# Logic_probe.net
KiCad netlist of a schematic drawn in EAGLE
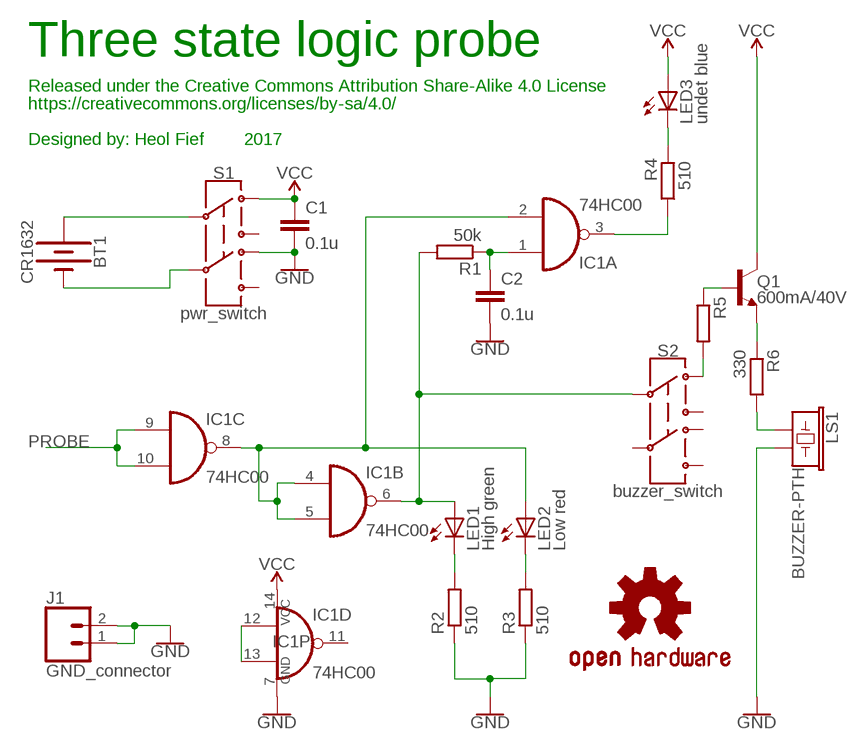
[diagram p0: schematic, sheet 1]

(export (version "E")
  (design (tool "Eeschema 10.0.6"))
  (components
    (comp (ref "BT1")
      (value "CR1632")
      (footprint "eagle-import:BATTCON_12MM_PTH")
      (libsource (lib "eagle-import") (part "BATTERY-12MM_PTH"))
    )
    (comp (ref "C1")
      (value "0.1u")
      (footprint "eagle-import:C0805")
      (libsource (lib "eagle-import") (part "C-EUC0805"))
    )
    (comp (ref "C2")
      (value "0.1u")
      (footprint "eagle-import:C0805")
      (libsource (lib "eagle-import") (part "C-EUC0805"))
    )
    (comp (ref "IC1")
      (value "74HC00")
      (footprint "eagle-import:SO14")
      (libsource (lib "eagle-import") (part "7400DHC"))
    )
    (comp (ref "J1")
      (value "GND_connector")
      (footprint "eagle-import:MOLEX-1X2")
      (libsource (lib "eagle-import") (part "CONN_02POLAR"))
    )
    (comp (ref "LED1")
      (value "High green")
      (footprint "eagle-import:1206")
      (libsource (lib "eagle-import") (part "LEDSMT1206"))
    )
    (comp (ref "LED2")
      (value "Low red")
      (footprint "eagle-import:1206")
      (libsource (lib "eagle-import") (part "LEDSMT1206"))
    )
    (comp (ref "LED3")
      (value "undet blue")
      (footprint "eagle-import:1206")
      (libsource (lib "eagle-import") (part "LEDSMT1206"))
    )
    (comp (ref "LOGO1")
      (value "OSHW-LOGOL")
      (footprint "eagle-import:OSHW-LOGO-L")
      (libsource (lib "eagle-import") (part "OSHW-LOGOL"))
    )
    (comp (ref "LS1")
      (value "BUZZER-PTH")
      (footprint "eagle-import:BUZZER-12MM")
      (libsource (lib "eagle-import") (part "BUZZER-PTH"))
    )
    (comp (ref "Q1")
      (value "600mA/40V")
      (footprint "eagle-import:SOT23-3")
      (libsource (lib "eagle-import") (part "TRANS_NPN-MMBT2222AL"))
    )
    (comp (ref "R1")
      (value "50k")
      (footprint "eagle-import:R1206")
      (libsource (lib "eagle-import") (part "R-EU_R1206"))
    )
    (comp (ref "R2")
      (value "510")
      (footprint "eagle-import:R0805")
      (libsource (lib "eagle-import") (part "R-EU_R0805"))
    )
    (comp (ref "R3")
      (value "510")
      (footprint "eagle-import:R0805")
      (libsource (lib "eagle-import") (part "R-EU_R0805"))
    )
    (comp (ref "R4")
      (value "510")
      (footprint "eagle-import:R0805")
      (libsource (lib "eagle-import") (part "R-EU_R0805"))
    )
    (comp (ref "R5")
      (value "R-EU_R1206")
      (footprint "eagle-import:R1206")
      (libsource (lib "eagle-import") (part "R-EU_R1206"))
    )
    (comp (ref "R6")
      (value "330")
      (footprint "eagle-import:R1206")
      (libsource (lib "eagle-import") (part "R-EU_R1206"))
    )
    (comp (ref "S1")
      (value "pwr_switch")
      (footprint "eagle-import:SWITCH_DPDT_SMD_AYZ0202")
      (libsource (lib "eagle-import") (part "SWITCH-DPDT-SMD-AYZ0202"))
    )
    (comp (ref "S2")
      (value "buzzer_switch")
      (footprint "eagle-import:SWITCH_DPDT_SMD_AYZ0202")
      (libsource (lib "eagle-import") (part "SWITCH-DPDT-SMD-AYZ0202"))
    )
  )
  (nets
    (net (code "1") (name "/PROBE") (class "Default")
      (node (ref "IC1") (pin "10") (pinfunction "I1_10") (pintype "input"))
      (node (ref "IC1") (pin "9") (pinfunction "I0_9") (pintype "input"))
    )
    (net (code "2") (name "GND") (class "Default")
      (node (ref "C1") (pin "2") (pinfunction "2_2") (pintype "passive"))
      (node (ref "C2") (pin "2") (pinfunction "2_2") (pintype "passive"))
      (node (ref "IC1") (pin "7") (pinfunction "GND_7") (pintype "power_in"))
      (node (ref "J1") (pin "1") (pinfunction "1_1") (pintype "passive"))
      (node (ref "J1") (pin "2") (pinfunction "2_2") (pintype "passive"))
      (node (ref "LS1") (pin "-") (pinfunction "2_-") (pintype "passive"))
      (node (ref "R2") (pin "1") (pinfunction "1_1") (pintype "passive"))
      (node (ref "R3") (pin "1") (pinfunction "1_1") (pintype "passive"))
      (node (ref "S1") (pin "4") (pinfunction "4_4") (pintype "bidirectional"))
    )
    (net (code "3") (name "Net-(BT1-+)") (class "Default")
      (node (ref "BT1") (pin "VCC@1") (pinfunction "+_VCC@1") (pintype "power_in"))
      (node (ref "S1") (pin "2") (pinfunction "2_2") (pintype "bidirectional"))
    )
    (net (code "4") (name "Net-(BT1--)") (class "Default")
      (node (ref "BT1") (pin "GND") (pinfunction "-_GND") (pintype "power_in"))
      (node (ref "S1") (pin "5") (pinfunction "5_5") (pintype "bidirectional"))
    )
    (net (code "5") (name "Net-(IC1A-I0)") (class "Default")
      (node (ref "C2") (pin "1") (pinfunction "1_1") (pintype "passive"))
      (node (ref "IC1") (pin "1") (pinfunction "I0_1") (pintype "input"))
      (node (ref "R1") (pin "1") (pinfunction "1_1") (pintype "passive"))
    )
    (net (code "6") (name "Net-(IC1A-I1)") (class "Default")
      (node (ref "IC1") (pin "2") (pinfunction "I1_2") (pintype "input"))
      (node (ref "IC1") (pin "4") (pinfunction "I0_4") (pintype "input"))
      (node (ref "IC1") (pin "5") (pinfunction "I1_5") (pintype "input"))
      (node (ref "IC1") (pin "8") (pinfunction "O_8") (pintype "output"))
      (node (ref "LED2") (pin "A") (pinfunction "A_A") (pintype "passive"))
    )
    (net (code "7") (name "Net-(IC1A-O)") (class "Default")
      (node (ref "IC1") (pin "3") (pinfunction "O_3") (pintype "output"))
      (node (ref "R4") (pin "1") (pinfunction "1_1") (pintype "passive"))
    )
    (net (code "8") (name "Net-(IC1B-O)") (class "Default")
      (node (ref "IC1") (pin "6") (pinfunction "O_6") (pintype "output"))
      (node (ref "LED1") (pin "A") (pinfunction "A_A") (pintype "passive"))
      (node (ref "R1") (pin "2") (pinfunction "2_2") (pintype "passive"))
      (node (ref "S2") (pin "2") (pinfunction "2_2") (pintype "bidirectional"))
    )
    (net (code "9") (name "Net-(IC1D-I0)") (class "Default")
      (node (ref "IC1") (pin "12") (pinfunction "I0_12") (pintype "input"))
      (node (ref "IC1") (pin "13") (pinfunction "I1_13") (pintype "input"))
    )
    (net (code "10") (name "Net-(LED1-PadC)") (class "Default")
      (node (ref "LED1") (pin "C") (pinfunction "C_C") (pintype "passive"))
      (node (ref "R2") (pin "2") (pinfunction "2_2") (pintype "passive"))
    )
    (net (code "11") (name "Net-(LED2-PadC)") (class "Default")
      (node (ref "LED2") (pin "C") (pinfunction "C_C") (pintype "passive"))
      (node (ref "R3") (pin "2") (pinfunction "2_2") (pintype "passive"))
    )
    (net (code "12") (name "Net-(LED3-PadC)") (class "Default")
      (node (ref "LED3") (pin "C") (pinfunction "C_C") (pintype "passive"))
      (node (ref "R4") (pin "2") (pinfunction "2_2") (pintype "passive"))
    )
    (net (code "13") (name "Net-(LS1-1)") (class "Default")
      (node (ref "LS1") (pin "+") (pinfunction "1_+") (pintype "passive"))
      (node (ref "R6") (pin "2") (pinfunction "2_2") (pintype "passive"))
    )
    (net (code "14") (name "Net-(Q1-B)") (class "Default")
      (node (ref "Q1") (pin "1") (pinfunction "B_1") (pintype "passive"))
      (node (ref "R5") (pin "1") (pinfunction "1_1") (pintype "passive"))
    )
    (net (code "15") (name "Net-(Q1-E)") (class "Default")
      (node (ref "Q1") (pin "2") (pinfunction "E_2") (pintype "passive"))
      (node (ref "R6") (pin "1") (pinfunction "1_1") (pintype "passive"))
    )
    (net (code "16") (name "Net-(R5-Pad2)") (class "Default")
      (node (ref "R5") (pin "2") (pinfunction "2_2") (pintype "passive"))
      (node (ref "S2") (pin "1") (pinfunction "1_1") (pintype "bidirectional"))
    )
    (net (code "17") (name "VCC") (class "Default")
      (node (ref "C1") (pin "1") (pinfunction "1_1") (pintype "passive"))
      (node (ref "IC1") (pin "14") (pinfunction "VCC_14") (pintype "power_in"))
      (node (ref "LED3") (pin "A") (pinfunction "A_A") (pintype "passive"))
      (node (ref "Q1") (pin "3") (pinfunction "C_3") (pintype "passive"))
      (node (ref "S1") (pin "1") (pinfunction "1_1") (pintype "bidirectional"))
    )
    (net (code "18") (name "unconnected-(IC1D-O-Pad11)") (class "Default")
      (node (ref "IC1") (pin "11") (pinfunction "O_11") (pintype "output"))
    )
    (net (code "19") (name "unconnected-(S1-Pad3)") (class "Default")
      (node (ref "S1") (pin "3") (pinfunction "3_3") (pintype "bidirectional"))
    )
    (net (code "20") (name "unconnected-(S1-Pad6)") (class "Default")
      (node (ref "S1") (pin "6") (pinfunction "6_6") (pintype "bidirectional"))
    )
    (net (code "21") (name "unconnected-(S2-Pad3)") (class "Default")
      (node (ref "S2") (pin "3") (pinfunction "3_3") (pintype "bidirectional"))
    )
    (net (code "22") (name "unconnected-(S2-Pad4)") (class "Default")
      (node (ref "S2") (pin "4") (pinfunction "4_4") (pintype "bidirectional"))
    )
    (net (code "23") (name "unconnected-(S2-Pad5)") (class "Default")
      (node (ref "S2") (pin "5") (pinfunction "5_5") (pintype "bidirectional"))
    )
    (net (code "24") (name "unconnected-(S2-Pad6)") (class "Default")
      (node (ref "S2") (pin "6") (pinfunction "6_6") (pintype "bidirectional"))
    )
  )
)
